# Constant_Current_Load.net
KiCad netlist of a schematic drawn in EAGLE
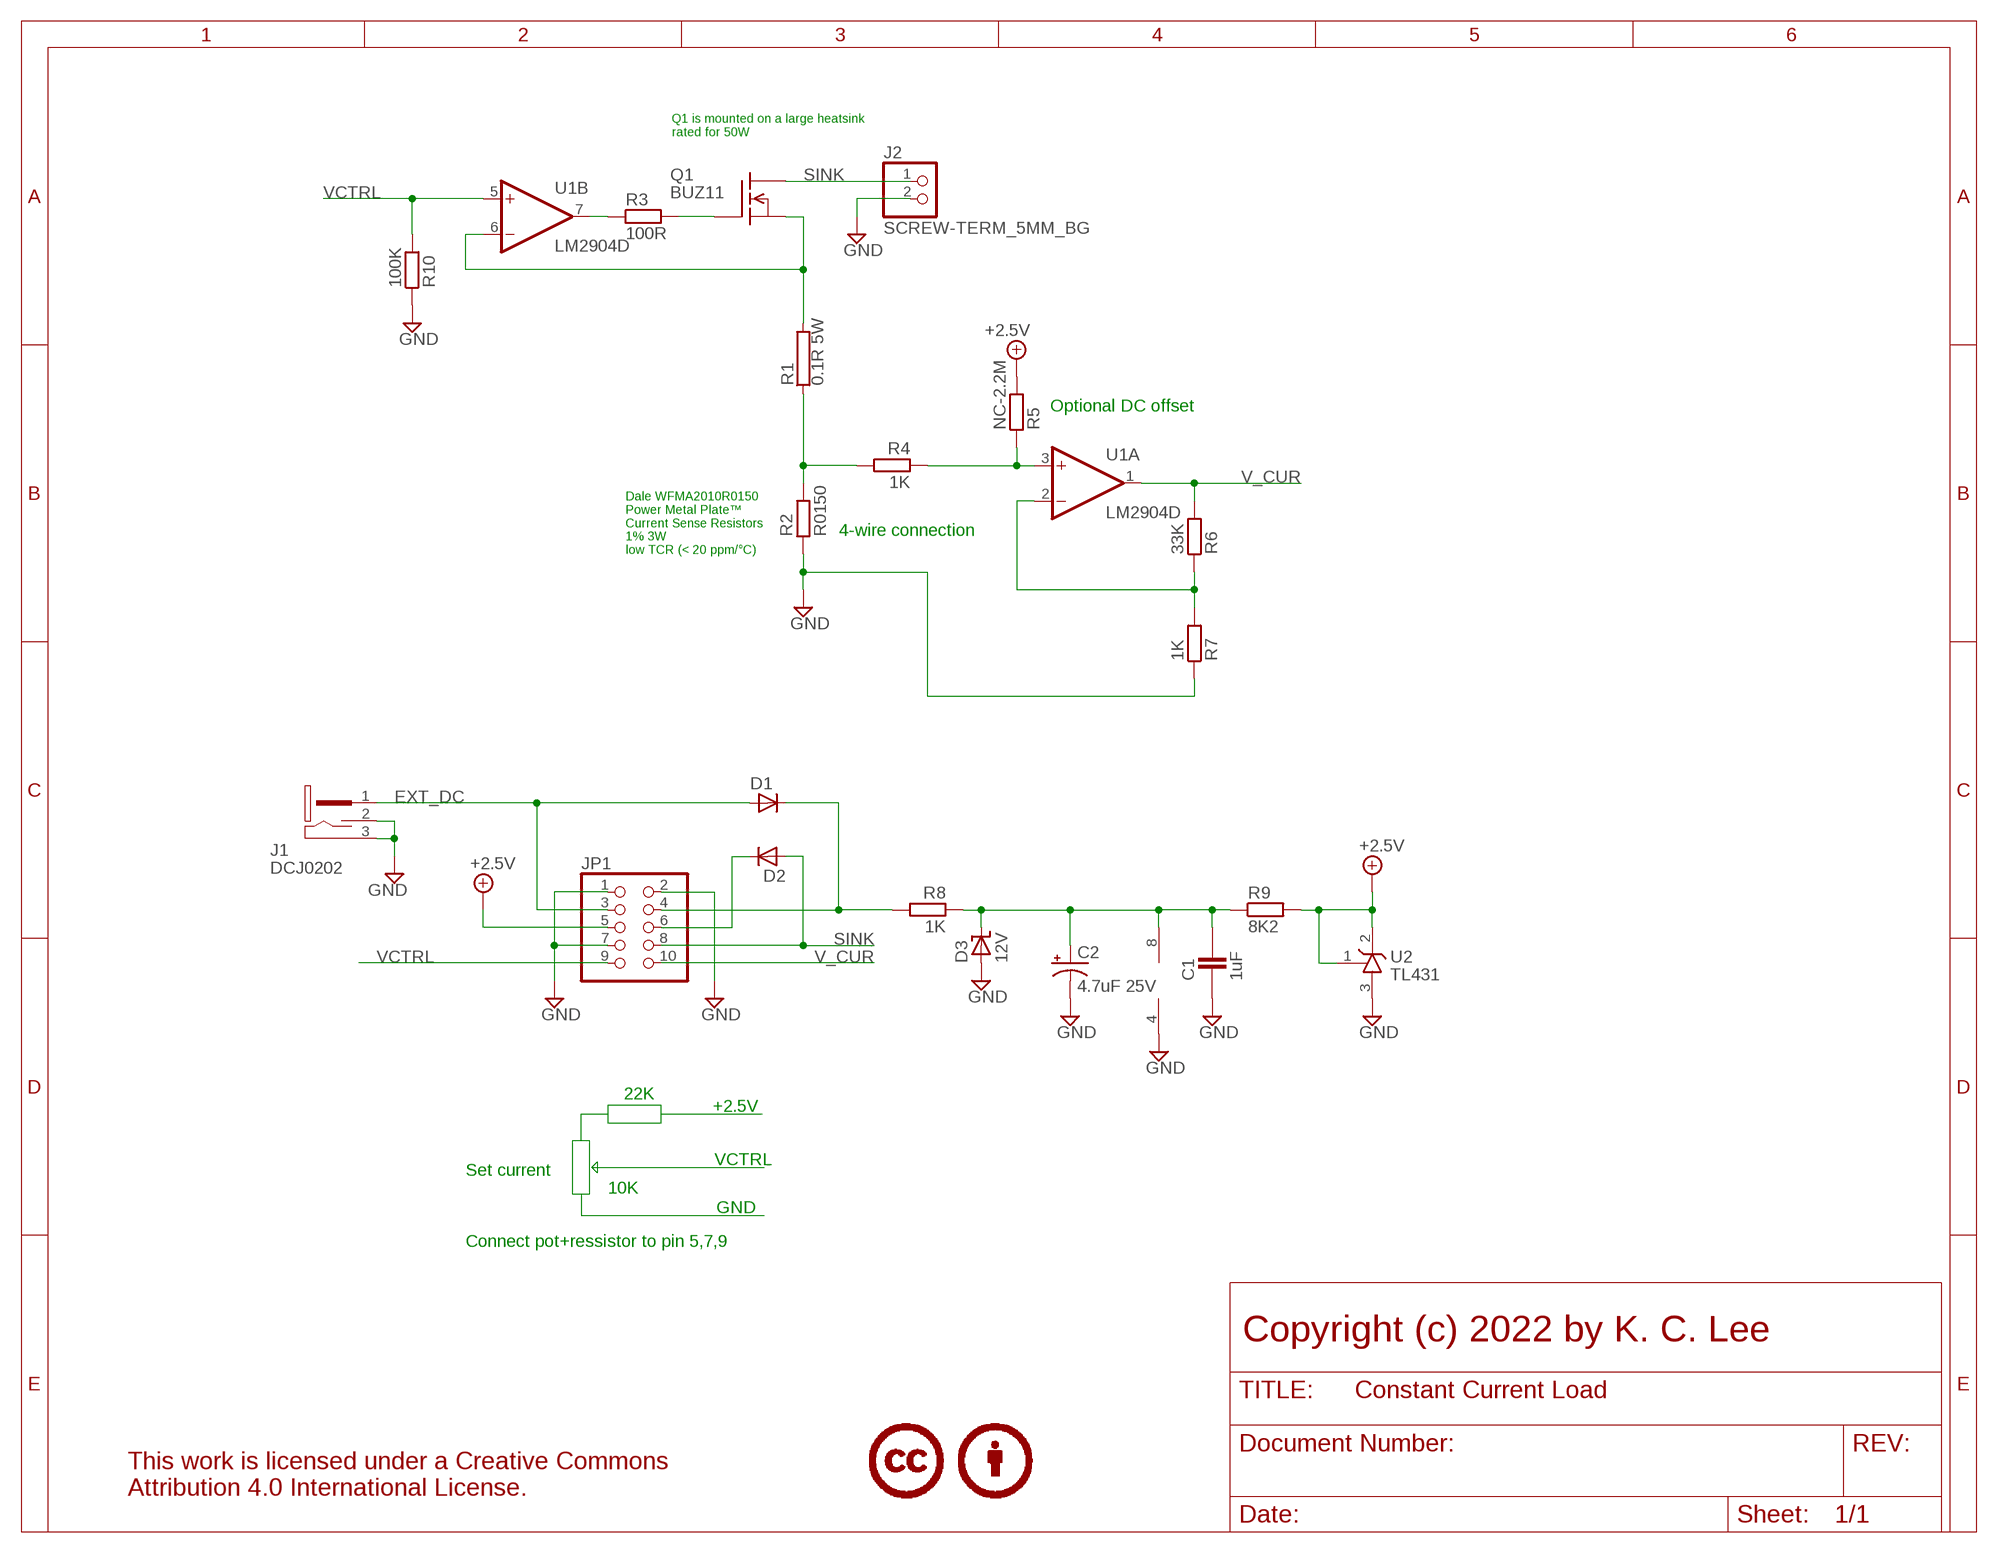
[diagram p0: schematic, sheet 1]

(export (version "E")
  (design (tool "Eeschema 10.0.6"))
  (components
    (comp (ref "C1")
      (value "1uF")
      (footprint "eagle-import:CAPC1608X92N")
      (libsource (lib "eagle-import") (part "CAPACITOR_0603"))
    )
    (comp (ref "C2")
      (value "4.7uF 25V")
      (footprint "eagle-import:E5-6")
      (libsource (lib "eagle-import") (part "CPOL-USE5-6"))
    )
    (comp (ref "D1")
      (value "DIODE_SOT-23")
      (footprint "eagle-import:SOT95P280X135-3N")
      (libsource (lib "eagle-import") (part "DIODE_SOT-23"))
    )
    (comp (ref "D2")
      (value "DIODE_SOT-23")
      (footprint "eagle-import:SOT95P280X135-3N")
      (libsource (lib "eagle-import") (part "DIODE_SOT-23"))
    )
    (comp (ref "D3")
      (value "12V")
      (footprint "eagle-import:SOT95P280X135-3N")
      (libsource (lib "eagle-import") (part "ZENER_SOT-23"))
    )
    (comp (ref "J1")
      (value "DCJ0202")
      (footprint "eagle-import:DCJ0202-SLOTTED")
      (libsource (lib "eagle-import") (part "DCJ0202"))
    )
    (comp (ref "J2")
      (value "SCREW-TERM_5MM_BG")
      (footprint "eagle-import:1X02-5MM-BG")
      (libsource (lib "eagle-import") (part "SCREW-TERM_5MM_BG"))
    )
    (comp (ref "JP1")
      (value "PINHD-2X5_2.54-W/PLUG")
      (footprint "eagle-import:2X05-W_PLUG")
      (libsource (lib "eagle-import") (part "PINHD-2X5_2.54-W/PLUG"))
    )
    (comp (ref "LICENSE1")
      (value "CC-BY50%")
      (footprint "eagle-import:CC-BY-50")
      (libsource (lib "eagle-import") (part "CC-BY50%"))
    )
    (comp (ref "Q1")
      (value "BUZ11")
      (footprint "eagle-import:TO220")
      (libsource (lib "eagle-import") (part "BUZ11"))
    )
    (comp (ref "R1")
      (value "0.1R 5W")
      (footprint "eagle-import:HPS923")
      (libsource (lib "eagle-import") (part "RHPS923"))
    )
    (comp (ref "R2")
      (value "R0150")
      (footprint "eagle-import:RESC5025X70N")
      (libsource (lib "eagle-import") (part "RESISTOR_2010"))
    )
    (comp (ref "R3")
      (value "100R")
      (footprint "eagle-import:RESC2012X70N")
      (libsource (lib "eagle-import") (part "RESISTOR_0805"))
    )
    (comp (ref "R4")
      (value "1K")
      (footprint "eagle-import:RESC1608X55N")
      (libsource (lib "eagle-import") (part "RESISTOR_0603"))
    )
    (comp (ref "R5")
      (value "NC-2.2M")
      (footprint "eagle-import:RESC1608X55N")
      (libsource (lib "eagle-import") (part "RESISTOR_0603"))
    )
    (comp (ref "R6")
      (value "33K")
      (footprint "eagle-import:RESC1608X55N")
      (libsource (lib "eagle-import") (part "RESISTOR_0603"))
    )
    (comp (ref "R7")
      (value "1K")
      (footprint "eagle-import:RESC1608X55N")
      (libsource (lib "eagle-import") (part "RESISTOR_0603"))
    )
    (comp (ref "R8")
      (value "1K")
      (footprint "eagle-import:RESC2012X70N")
      (libsource (lib "eagle-import") (part "RESISTOR_0805"))
    )
    (comp (ref "R9")
      (value "8K2")
      (footprint "eagle-import:RESC2012X70N")
      (libsource (lib "eagle-import") (part "RESISTOR_0805"))
    )
    (comp (ref "R10")
      (value "100K")
      (footprint "eagle-import:RESC1608X55N")
      (libsource (lib "eagle-import") (part "RESISTOR_0603"))
    )
    (comp (ref "U1")
      (value "LM2904D")
      (footprint "eagle-import:SO08")
      (libsource (lib "eagle-import") (part "LM358D"))
    )
    (comp (ref "U2")
      (value "TL431")
      (footprint "eagle-import:SOT95P280X135-3N")
      (libsource (lib "eagle-import") (part "TL_431DBZ"))
    )
  )
  (nets
    (net (code "1") (name "+2.5V") (class "Default")
      (node (ref "JP1") (pin "5") (pinfunction "5_5") (pintype "passive"))
      (node (ref "R5") (pin "2") (pinfunction "2_2") (pintype "passive"))
      (node (ref "R9") (pin "2") (pinfunction "2_2") (pintype "passive"))
      (node (ref "U2") (pin "1") (pinfunction "R_1") (pintype "passive"))
      (node (ref "U2") (pin "2") (pinfunction "C_2") (pintype "passive"))
    )
    (net (code "2") (name "/EXT_DC") (class "Default")
      (node (ref "D1") (pin "1") (pinfunction "A_1") (pintype "passive"))
      (node (ref "J1") (pin "1") (pinfunction "1_1") (pintype "passive"))
      (node (ref "JP1") (pin "3") (pinfunction "3_3") (pintype "passive"))
    )
    (net (code "3") (name "/SINK") (class "Default")
      (node (ref "D2") (pin "1") (pinfunction "A_1") (pintype "passive"))
      (node (ref "J2") (pin "1") (pinfunction "1_1") (pintype "passive"))
      (node (ref "JP1") (pin "8") (pinfunction "8_8") (pintype "passive"))
      (node (ref "Q1") (pin "2") (pinfunction "D_2") (pintype "passive"))
    )
    (net (code "4") (name "/VCTRL") (class "Default")
      (node (ref "JP1") (pin "9") (pinfunction "9_9") (pintype "passive"))
      (node (ref "R10") (pin "2") (pinfunction "2_2") (pintype "passive"))
      (node (ref "U1") (pin "5") (pinfunction "+IN_5") (pintype "input"))
    )
    (net (code "5") (name "/V_CUR") (class "Default")
      (node (ref "JP1") (pin "10") (pinfunction "10_10") (pintype "passive"))
      (node (ref "R6") (pin "2") (pinfunction "2_2") (pintype "passive"))
      (node (ref "U1") (pin "1") (pinfunction "OUT_1") (pintype "output"))
    )
    (net (code "6") (name "GND") (class "Default")
      (node (ref "C1") (pin "1") (pinfunction "1_1") (pintype "passive"))
      (node (ref "C2") (pin "-") (pinfunction "-_-") (pintype "passive"))
      (node (ref "D3") (pin "1") (pinfunction "A_1") (pintype "passive"))
      (node (ref "J1") (pin "2") (pinfunction "2_2") (pintype "passive"))
      (node (ref "J1") (pin "3") (pinfunction "3_3") (pintype "passive"))
      (node (ref "J2") (pin "2") (pinfunction "2_2") (pintype "passive"))
      (node (ref "JP1") (pin "1") (pinfunction "1_1") (pintype "passive"))
      (node (ref "JP1") (pin "2") (pinfunction "2_2") (pintype "passive"))
      (node (ref "JP1") (pin "7") (pinfunction "7_7") (pintype "passive"))
      (node (ref "R10") (pin "1") (pinfunction "1_1") (pintype "passive"))
      (node (ref "R2") (pin "1") (pinfunction "1_1") (pintype "passive"))
      (node (ref "R7") (pin "1") (pinfunction "1_1") (pintype "passive"))
      (node (ref "U1") (pin "4") (pinfunction "V-_4") (pintype "power_in"))
      (node (ref "U2") (pin "3") (pinfunction "A_3") (pintype "passive"))
    )
    (net (code "7") (name "Net-(D1-K)") (class "Default")
      (node (ref "D1") (pin "3") (pinfunction "K_3") (pintype "passive"))
      (node (ref "JP1") (pin "4") (pinfunction "4_4") (pintype "passive"))
      (node (ref "R8") (pin "2") (pinfunction "2_2") (pintype "passive"))
    )
    (net (code "8") (name "Net-(D2-K)") (class "Default")
      (node (ref "D2") (pin "3") (pinfunction "K_3") (pintype "passive"))
      (node (ref "JP1") (pin "6") (pinfunction "6_6") (pintype "passive"))
    )
    (net (code "9") (name "Net-(D3-K)") (class "Default")
      (node (ref "C1") (pin "2") (pinfunction "2_2") (pintype "passive"))
      (node (ref "C2") (pin "+") (pinfunction "+_+") (pintype "passive"))
      (node (ref "D3") (pin "3") (pinfunction "K_3") (pintype "passive"))
      (node (ref "R8") (pin "1") (pinfunction "1_1") (pintype "passive"))
      (node (ref "R9") (pin "1") (pinfunction "1_1") (pintype "passive"))
      (node (ref "U1") (pin "8") (pinfunction "V+_8") (pintype "power_in"))
    )
    (net (code "10") (name "Net-(Q1-G)") (class "Default")
      (node (ref "Q1") (pin "1") (pinfunction "G_1") (pintype "passive"))
      (node (ref "R3") (pin "2") (pinfunction "2_2") (pintype "passive"))
    )
    (net (code "11") (name "Net-(Q1-S)") (class "Default")
      (node (ref "Q1") (pin "3") (pinfunction "S_3") (pintype "passive"))
      (node (ref "R1") (pin "2") (pinfunction "2_2") (pintype "passive"))
      (node (ref "U1") (pin "6") (pinfunction "-IN_6") (pintype "input"))
    )
    (net (code "12") (name "Net-(R1-Pad1)") (class "Default")
      (node (ref "R1") (pin "1") (pinfunction "1_1") (pintype "passive"))
      (node (ref "R2") (pin "2") (pinfunction "2_2") (pintype "passive"))
      (node (ref "R4") (pin "2") (pinfunction "2_2") (pintype "passive"))
    )
    (net (code "13") (name "Net-(U1A-+IN)") (class "Default")
      (node (ref "R4") (pin "1") (pinfunction "1_1") (pintype "passive"))
      (node (ref "R5") (pin "1") (pinfunction "1_1") (pintype "passive"))
      (node (ref "U1") (pin "3") (pinfunction "+IN_3") (pintype "input"))
    )
    (net (code "14") (name "Net-(U1A--IN)") (class "Default")
      (node (ref "R6") (pin "1") (pinfunction "1_1") (pintype "passive"))
      (node (ref "R7") (pin "2") (pinfunction "2_2") (pintype "passive"))
      (node (ref "U1") (pin "2") (pinfunction "-IN_2") (pintype "input"))
    )
    (net (code "15") (name "Net-(U1B-OUT)") (class "Default")
      (node (ref "R3") (pin "1") (pinfunction "1_1") (pintype "passive"))
      (node (ref "U1") (pin "7") (pinfunction "OUT_7") (pintype "output"))
    )
  )
)
